# POWER.net
KiCad netlist of a schematic drawn in Altium Designer
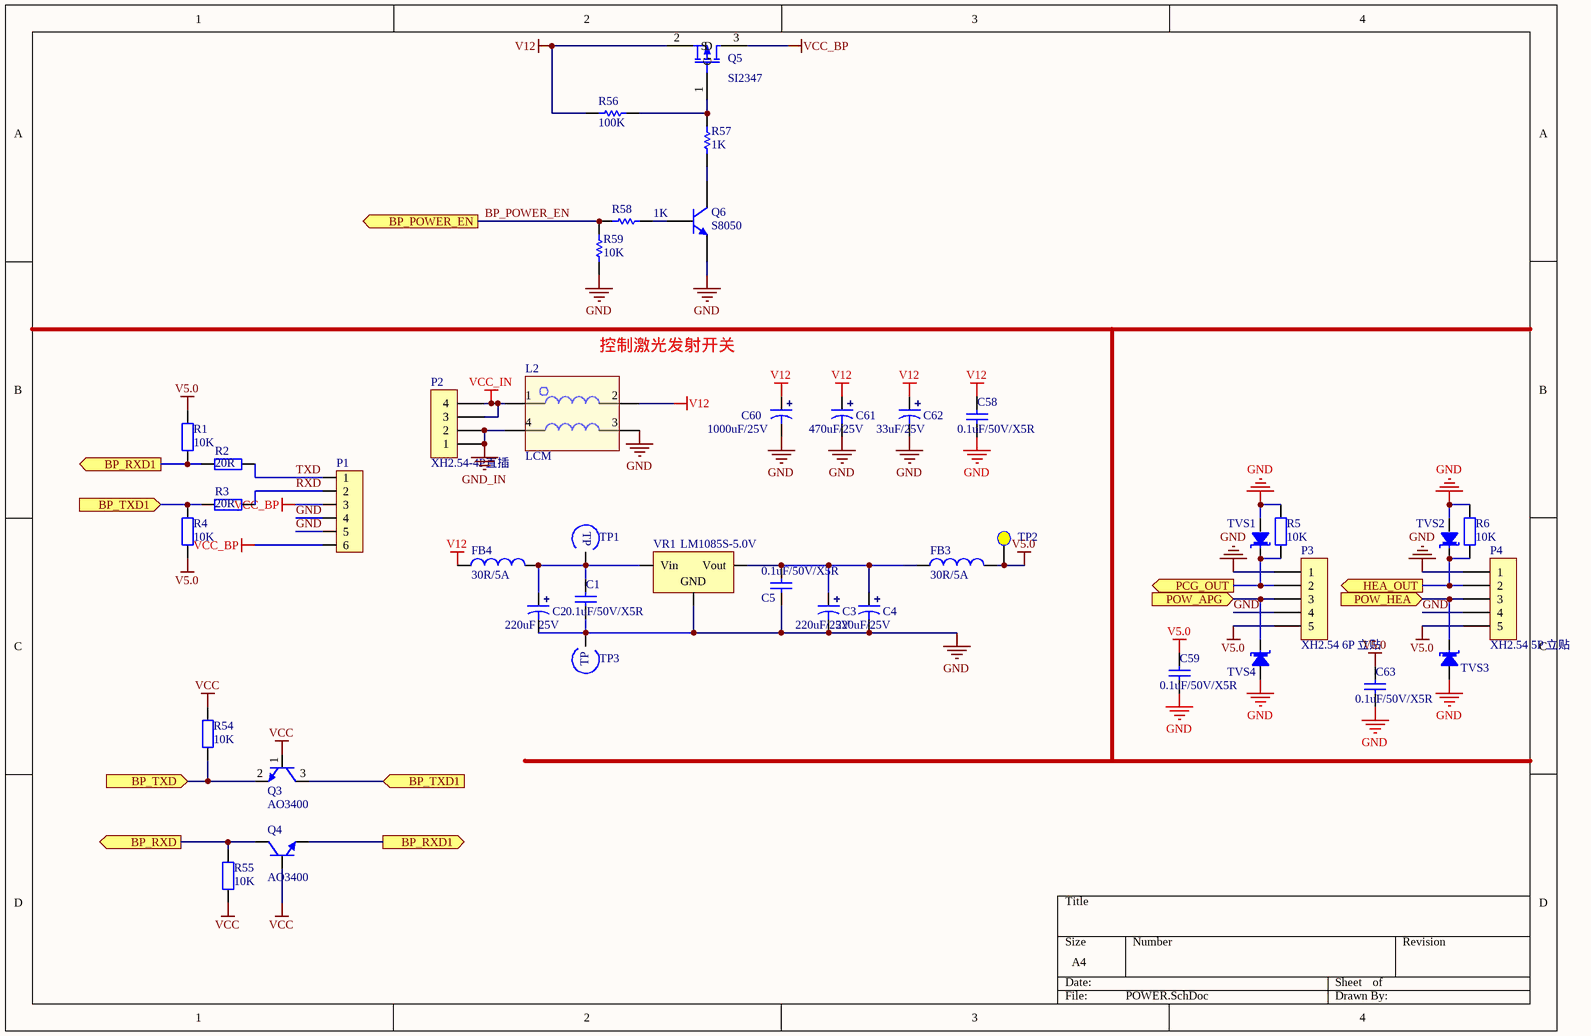
[diagram p0: POWER.SchDoc]

(export (version "E")
  (design (tool "Eeschema 10.0.6"))
  (components
    (comp (ref "C1")
      (value "0.1uF/50V/X5R")
      (footprint "SMD-0603C")
      (description "贴片电容 20%")
      (libsource (lib "XiaoyI") (part "CAP4"))
    )
    (comp (ref "C2")
      (value "220uF 25V")
      (footprint "SMD-6.3*7.7")
      (description "电解电容")
      (libsource (lib "XiaoyI") (part "CAP2"))
    )
    (comp (ref "C3")
      (value "220uF/25V")
      (footprint "SMD-6.3*7.7")
      (description "电解电容")
      (libsource (lib "XiaoyI") (part "CAP2"))
    )
    (comp (ref "C4")
      (value "220uF/25V")
      (footprint "SMD-6.3*7.7")
      (description "电解电容")
      (libsource (lib "XiaoyI") (part "CAP2"))
    )
    (comp (ref "C5")
      (value "0.1uF/50V/X5R")
      (footprint "SMD-0603C")
      (description "贴片电容 20%")
      (libsource (lib "XiaoyI") (part "CAP4"))
    )
    (comp (ref "C58")
      (value "0.1uF/50V/X5R")
      (footprint "SMD-0603C")
      (description "贴片电容 20%")
      (libsource (lib "XiaoyI") (part "CAP4"))
    )
    (comp (ref "C59")
      (value "0.1uF/50V/X5R")
      (footprint "SMD-0603C")
      (description "贴片电容 20%")
      (libsource (lib "XiaoyI") (part "CAP4"))
    )
    (comp (ref "C60")
      (value "1000uF/25V")
      (footprint "10*16")
      (description "电解电容")
      (libsource (lib "XiaoyI") (part "CAP2"))
    )
    (comp (ref "C61")
      (value "470uF/25V")
      (footprint "8*12")
      (description "电解电容")
      (libsource (lib "XiaoyI") (part "CAP2"))
    )
    (comp (ref "C62")
      (value "33uF/25V")
      (footprint "5*7")
      (description "电解电容")
      (libsource (lib "XiaoyI") (part "CAP2"))
    )
    (comp (ref "C63")
      (value "0.1uF/50V/X5R")
      (footprint "SMD-0603C")
      (description "贴片电容 20%")
      (libsource (lib "XiaoyI") (part "CAP4"))
    )
    (comp (ref "FB3")
      (value "30R/5A")
      (footprint "0603r")
      (description "Inductor")
      (fields (field (name "PUBLISHER") "Altium Limited"))
      (libsource (lib "Miscellaneous Devices") (part "Inductor"))
    )
    (comp (ref "FB4")
      (value "30R/5A")
      (footprint "0603r")
      (description "Inductor")
      (fields (field (name "PUBLISHER") "Altium Limited"))
      (libsource (lib "Miscellaneous Devices") (part "Inductor"))
    )
    (comp (ref "L2") (value "LCM") (footprint "LCM") (libsource (lib "stm32") (part "LCM")))
    (comp (ref "P1")
      (value "XH2.54 6P 立贴")
      (footprint "XH-2.54-6P-LI")
      (description "血压计接口")
      (libsource (lib "ABB") (part "SIP-6"))
    )
    (comp (ref "P2") (value "XH2.54-4P直插") (footprint "4X2.54MMZ") (libsource (lib "ABB") (part "SIP-4")))
    (comp (ref "P3")
      (value "XH2.54 6P 立贴")
      (footprint "XH-2.54-5P-LI")
      (description "颈动脉传感器接口")
      (libsource (lib "ABB") (part "SIP-5"))
    )
    (comp (ref "P4")
      (value "XH2.54 5P 立贴")
      (footprint "XH-2.54-5P-LI")
      (description "心音传感器接口")
      (libsource (lib "ABB") (part "SIP-5"))
    )
    (comp (ref "Q3")
      (value "AO3400")
      (footprint "SOT-23")
      (description "NPN")
      (libsource (lib "") (part "NPN-1_1"))
    )
    (comp (ref "Q4")
      (value "AO3400")
      (footprint "SOT-23")
      (description "NPN")
      (libsource (lib "XiaoyI") (part "NPN-1"))
    )
    (comp (ref "Q5")
      (value "SI2347")
      (footprint "SOT23-3")
      (description "P-Channel MOSFET")
      (fields (field (name "PUBLISHER") "Altium Limited"))
      (libsource (lib "Miscellaneous Devices") (part "MOSFET-P"))
    )
    (comp (ref "Q6")
      (value "S8050")
      (footprint "SOT23-3")
      (description "NPN Bipolar Transistor")
      (fields (field (name "PUBLISHER") "Altium Limited"))
      (libsource (lib "Miscellaneous Devices") (part "NPN"))
    )
    (comp (ref "R1")
      (value "10K")
      (footprint "SMD-0603")
      (description "贴片电阻 1%")
      (libsource (lib "") (part "RES2_1"))
    )
    (comp (ref "R2")
      (value "20R")
      (footprint "SMD-0603")
      (description "贴片电阻 1%")
      (libsource (lib "") (part "RES2_2"))
    )
    (comp (ref "R3")
      (value "20R")
      (footprint "SMD-0603")
      (description "贴片电阻 1%")
      (libsource (lib "") (part "RES2_2"))
    )
    (comp (ref "R4")
      (value "10K")
      (footprint "SMD-0603")
      (description "贴片电阻 1%")
      (libsource (lib "") (part "RES2_1"))
    )
    (comp (ref "R5")
      (value "10K")
      (footprint "SMD-0603")
      (description "贴片电阻 1%")
      (libsource (lib "") (part "RES2_1"))
    )
    (comp (ref "R6")
      (value "10K")
      (footprint "SMD-0603")
      (description "贴片电阻 1%")
      (libsource (lib "") (part "RES2_1"))
    )
    (comp (ref "R54")
      (value "10K")
      (footprint "SMD-0603")
      (description "贴片电阻 1%")
      (libsource (lib "XiaoyI") (part "RES2"))
    )
    (comp (ref "R55")
      (value "10K")
      (footprint "SMD-0603")
      (description "贴片电阻 1%")
      (libsource (lib "XiaoyI") (part "RES2"))
    )
    (comp (ref "R56")
      (value "100K")
      (footprint "0603R")
      (description "Resistor")
      (fields (field (name "PUBLISHER") "Altium Limited"))
      (libsource (lib "Miscellaneous Devices") (part "Res1"))
    )
    (comp (ref "R57")
      (value "1K")
      (footprint "0603R")
      (description "Resistor")
      (fields (field (name "PUBLISHER") "Altium Limited"))
      (libsource (lib "Miscellaneous Devices") (part "Res1"))
    )
    (comp (ref "R58")
      (value "1K")
      (footprint "0603R")
      (description "Resistor")
      (fields (field (name "PUBLISHER") "Altium Limited"))
      (libsource (lib "Miscellaneous Devices") (part "Res1"))
    )
    (comp (ref "R59")
      (value "10K")
      (footprint "0603R")
      (description "Resistor")
      (fields (field (name "PUBLISHER") "Altium Limited"))
      (libsource (lib "Miscellaneous Devices") (part "Res1"))
    )
    (comp (ref "TP1")
      (value "TP")
      (footprint "TP")
      (description "测试点")
      (libsource (lib "XiaoyI") (part "TP-1"))
    )
    (comp (ref "TP2")
      (value "TP")
      (footprint "TP")
      (description "测试点")
      (libsource (lib "ABB") (part "TP_POINT"))
    )
    (comp (ref "TP3")
      (value "TP")
      (footprint "TP")
      (description "测试点")
      (libsource (lib "XiaoyI") (part "TP-1"))
    )
    (comp (ref "TVS1")
      (value "TVS-S")
      (footprint "SOD-323")
      (description "单向TVS")
      (libsource (lib "XiaoyI") (part "TVS-S"))
    )
    (comp (ref "TVS2")
      (value "TVS-S")
      (footprint "SOD-323")
      (description "单向TVS")
      (libsource (lib "XiaoyI") (part "TVS-S"))
    )
    (comp (ref "TVS3")
      (value "TVS-S")
      (footprint "SOD-323")
      (description "单向TVS")
      (libsource (lib "") (part "TVS-S_1"))
    )
    (comp (ref "TVS4")
      (value "TVS-S")
      (footprint "SOD-323")
      (description "单向TVS")
      (libsource (lib "") (part "TVS-S_1"))
    )
    (comp (ref "VR1")
      (value "LM1085S-5.0V")
      (footprint "TO-263-3")
      (description "三端稳压器")
      (libsource (lib "XiaoyI") (part "LM1117"))
    )
  )
  (nets
    (net (code "1") (name "/BP_POWER_EN") (class "Default")
      (node (ref "R58") (pin "2") (pinfunction "2_2") (pintype "passive"))
      (node (ref "R59") (pin "1") (pinfunction "1_1") (pintype "passive"))
    )
    (net (code "2") (name "/BP_RXD") (class "Default")
      (node (ref "Q4") (pin "3") (pinfunction "C_3") (pintype "passive"))
      (node (ref "R55") (pin "2") (pinfunction "2_2") (pintype "passive"))
    )
    (net (code "3") (name "/BP_RXD1") (class "Default")
      (node (ref "Q4") (pin "2") (pinfunction "E_2") (pintype "passive"))
      (node (ref "R1") (pin "2") (pinfunction "2_2") (pintype "passive"))
      (node (ref "R2") (pin "2") (pinfunction "2_2") (pintype "passive"))
    )
    (net (code "4") (name "/BP_TXD") (class "Default")
      (node (ref "Q3") (pin "2") (pinfunction "E_2") (pintype "passive"))
      (node (ref "R54") (pin "1") (pinfunction "1_1") (pintype "passive"))
    )
    (net (code "5") (name "/BP_TXD1") (class "Default")
      (node (ref "Q3") (pin "3") (pinfunction "C_3") (pintype "passive"))
      (node (ref "R3") (pin "2") (pinfunction "2_2") (pintype "passive"))
      (node (ref "R4") (pin "1") (pinfunction "1_1") (pintype "passive"))
    )
    (net (code "6") (name "/HEA_OUT") (class "Default")
      (node (ref "P4") (pin "2") (pinfunction "2_2") (pintype "passive"))
      (node (ref "R6") (pin "2") (pinfunction "2_2") (pintype "passive"))
      (node (ref "TVS2") (pin "2") (pinfunction "B_2") (pintype "passive"))
    )
    (net (code "7") (name "/PCG_OUT") (class "Default")
      (node (ref "P3") (pin "2") (pinfunction "2_2") (pintype "passive"))
      (node (ref "R5") (pin "2") (pinfunction "2_2") (pintype "passive"))
      (node (ref "TVS1") (pin "2") (pinfunction "B_2") (pintype "passive"))
    )
    (net (code "8") (name "/POW_APG") (class "Default")
      (node (ref "P3") (pin "3") (pinfunction "3_3") (pintype "passive"))
      (node (ref "TVS4") (pin "2") (pinfunction "B_2") (pintype "passive"))
    )
    (net (code "9") (name "/POW_HEA") (class "Default")
      (node (ref "P4") (pin "3") (pinfunction "3_3") (pintype "passive"))
      (node (ref "TVS3") (pin "2") (pinfunction "B_2") (pintype "passive"))
    )
    (net (code "10") (name "/RXD") (class "Default")
      (node (ref "P1") (pin "2") (pinfunction "2_2") (pintype "passive"))
      (node (ref "R3") (pin "1") (pinfunction "1_1") (pintype "passive"))
    )
    (net (code "11") (name "/TXD") (class "Default")
      (node (ref "P1") (pin "1") (pinfunction "1_1") (pintype "passive"))
      (node (ref "R2") (pin "1") (pinfunction "1_1") (pintype "passive"))
    )
    (net (code "12") (name "GND") (class "Default")
      (node (ref "C1") (pin "1") (pinfunction "1_1") (pintype "passive"))
      (node (ref "C2") (pin "2") (pinfunction "2_2") (pintype "passive"))
      (node (ref "C3") (pin "2") (pinfunction "2_2") (pintype "passive"))
      (node (ref "C4") (pin "2") (pinfunction "2_2") (pintype "passive"))
      (node (ref "C5") (pin "1") (pinfunction "1_1") (pintype "passive"))
      (node (ref "C58") (pin "1") (pinfunction "1_1") (pintype "passive"))
      (node (ref "C59") (pin "1") (pinfunction "1_1") (pintype "passive"))
      (node (ref "C60") (pin "2") (pinfunction "2_2") (pintype "passive"))
      (node (ref "C61") (pin "2") (pinfunction "2_2") (pintype "passive"))
      (node (ref "C62") (pin "2") (pinfunction "2_2") (pintype "passive"))
      (node (ref "C63") (pin "1") (pinfunction "1_1") (pintype "passive"))
      (node (ref "L2") (pin "3") (pintype "passive"))
      (node (ref "P1") (pin "4") (pinfunction "4_4") (pintype "passive"))
      (node (ref "P1") (pin "5") (pinfunction "5_5") (pintype "passive"))
      (node (ref "P3") (pin "1") (pinfunction "1_1") (pintype "passive"))
      (node (ref "P3") (pin "4") (pinfunction "4_4") (pintype "passive"))
      (node (ref "P4") (pin "1") (pinfunction "1_1") (pintype "passive"))
      (node (ref "P4") (pin "4") (pinfunction "4_4") (pintype "passive"))
      (node (ref "Q6") (pin "2") (pinfunction "E_2") (pintype "passive"))
      (node (ref "R5") (pin "1") (pinfunction "1_1") (pintype "passive"))
      (node (ref "R59") (pin "2") (pinfunction "2_2") (pintype "passive"))
      (node (ref "R6") (pin "1") (pinfunction "1_1") (pintype "passive"))
      (node (ref "TP3") (pin "1") (pinfunction "1_1") (pintype "passive"))
      (node (ref "TVS1") (pin "1") (pinfunction "A_1") (pintype "passive"))
      (node (ref "TVS2") (pin "1") (pinfunction "A_1") (pintype "passive"))
      (node (ref "TVS3") (pin "1") (pinfunction "A_1") (pintype "passive"))
      (node (ref "TVS4") (pin "1") (pinfunction "A_1") (pintype "passive"))
      (node (ref "VR1") (pin "1") (pinfunction "GND_1") (pintype "passive"))
    )
    (net (code "13") (name "GND_IN") (class "Default")
      (node (ref "L2") (pin "4") (pintype "passive"))
      (node (ref "P2") (pin "1") (pinfunction "1_1") (pintype "passive"))
      (node (ref "P2") (pin "2") (pinfunction "2_2") (pintype "passive"))
    )
    (net (code "14") (name "Net-(Q5-G)") (class "Default")
      (node (ref "Q5") (pin "1") (pinfunction "G_1") (pintype "passive"))
      (node (ref "R56") (pin "1") (pinfunction "1_1") (pintype "passive"))
      (node (ref "R57") (pin "2") (pinfunction "2_2") (pintype "passive"))
    )
    (net (code "15") (name "Net-(Q6-B)") (class "Default")
      (node (ref "Q6") (pin "1") (pinfunction "B_1") (pintype "passive"))
      (node (ref "R58") (pin "1") (pinfunction "1_1") (pintype "passive"))
    )
    (net (code "16") (name "Net-(Q6-C)") (class "Default")
      (node (ref "Q6") (pin "3") (pinfunction "C_3") (pintype "passive"))
      (node (ref "R57") (pin "1") (pinfunction "1_1") (pintype "passive"))
    )
    (net (code "17") (name "Net-(VR1-Vin)") (class "Default")
      (node (ref "C1") (pin "2") (pinfunction "2_2") (pintype "passive"))
      (node (ref "C2") (pin "1") (pinfunction "1_1") (pintype "passive"))
      (node (ref "FB4") (pin "2") (pinfunction "2_2") (pintype "passive"))
      (node (ref "TP1") (pin "1") (pinfunction "1_1") (pintype "passive"))
      (node (ref "VR1") (pin "3") (pinfunction "Vin_3") (pintype "passive"))
    )
    (net (code "18") (name "Net-(VR1-Vout)") (class "Default")
      (node (ref "C3") (pin "1") (pinfunction "1_1") (pintype "passive"))
      (node (ref "C4") (pin "1") (pinfunction "1_1") (pintype "passive"))
      (node (ref "C5") (pin "2") (pinfunction "2_2") (pintype "passive"))
      (node (ref "FB3") (pin "1") (pinfunction "1_1") (pintype "passive"))
      (node (ref "VR1") (pin "2") (pinfunction "Vout_2") (pintype "passive"))
    )
    (net (code "19") (name "V5.0") (class "Default")
      (node (ref "C59") (pin "2") (pinfunction "2_2") (pintype "passive"))
      (node (ref "C63") (pin "2") (pinfunction "2_2") (pintype "passive"))
      (node (ref "FB3") (pin "2") (pinfunction "2_2") (pintype "passive"))
      (node (ref "P3") (pin "5") (pinfunction "5_5") (pintype "passive"))
      (node (ref "P4") (pin "5") (pinfunction "5_5") (pintype "passive"))
      (node (ref "R1") (pin "1") (pinfunction "1_1") (pintype "passive"))
      (node (ref "R4") (pin "2") (pinfunction "2_2") (pintype "passive"))
      (node (ref "TP2") (pin "1") (pinfunction "TP_1") (pintype "power_in"))
    )
    (net (code "20") (name "V12") (class "Default")
      (node (ref "C58") (pin "2") (pinfunction "2_2") (pintype "passive"))
      (node (ref "C60") (pin "1") (pinfunction "1_1") (pintype "passive"))
      (node (ref "C61") (pin "1") (pinfunction "1_1") (pintype "passive"))
      (node (ref "C62") (pin "1") (pinfunction "1_1") (pintype "passive"))
      (node (ref "FB4") (pin "1") (pinfunction "1_1") (pintype "passive"))
      (node (ref "L2") (pin "2") (pintype "passive"))
      (node (ref "Q5") (pin "2") (pinfunction "S_2") (pintype "passive"))
      (node (ref "R56") (pin "2") (pinfunction "2_2") (pintype "passive"))
    )
    (net (code "21") (name "VCC") (class "Default")
      (node (ref "Q3") (pin "1") (pinfunction "B_1") (pintype "passive"))
      (node (ref "Q4") (pin "1") (pinfunction "B_1") (pintype "passive"))
      (node (ref "R54") (pin "2") (pinfunction "2_2") (pintype "passive"))
      (node (ref "R55") (pin "1") (pinfunction "1_1") (pintype "passive"))
    )
    (net (code "22") (name "VCC_BP") (class "Default")
      (node (ref "P1") (pin "3") (pinfunction "3_3") (pintype "passive"))
      (node (ref "P1") (pin "6") (pinfunction "6_6") (pintype "passive"))
      (node (ref "Q5") (pin "3") (pinfunction "D_3") (pintype "passive"))
    )
    (net (code "23") (name "VCC_IN") (class "Default")
      (node (ref "L2") (pin "1") (pintype "passive"))
      (node (ref "P2") (pin "3") (pinfunction "3_3") (pintype "passive"))
      (node (ref "P2") (pin "4") (pinfunction "4_4") (pintype "passive"))
    )
  )
)
